# Figure1.net
KiCad netlist of a schematic drawn in Altium Designer
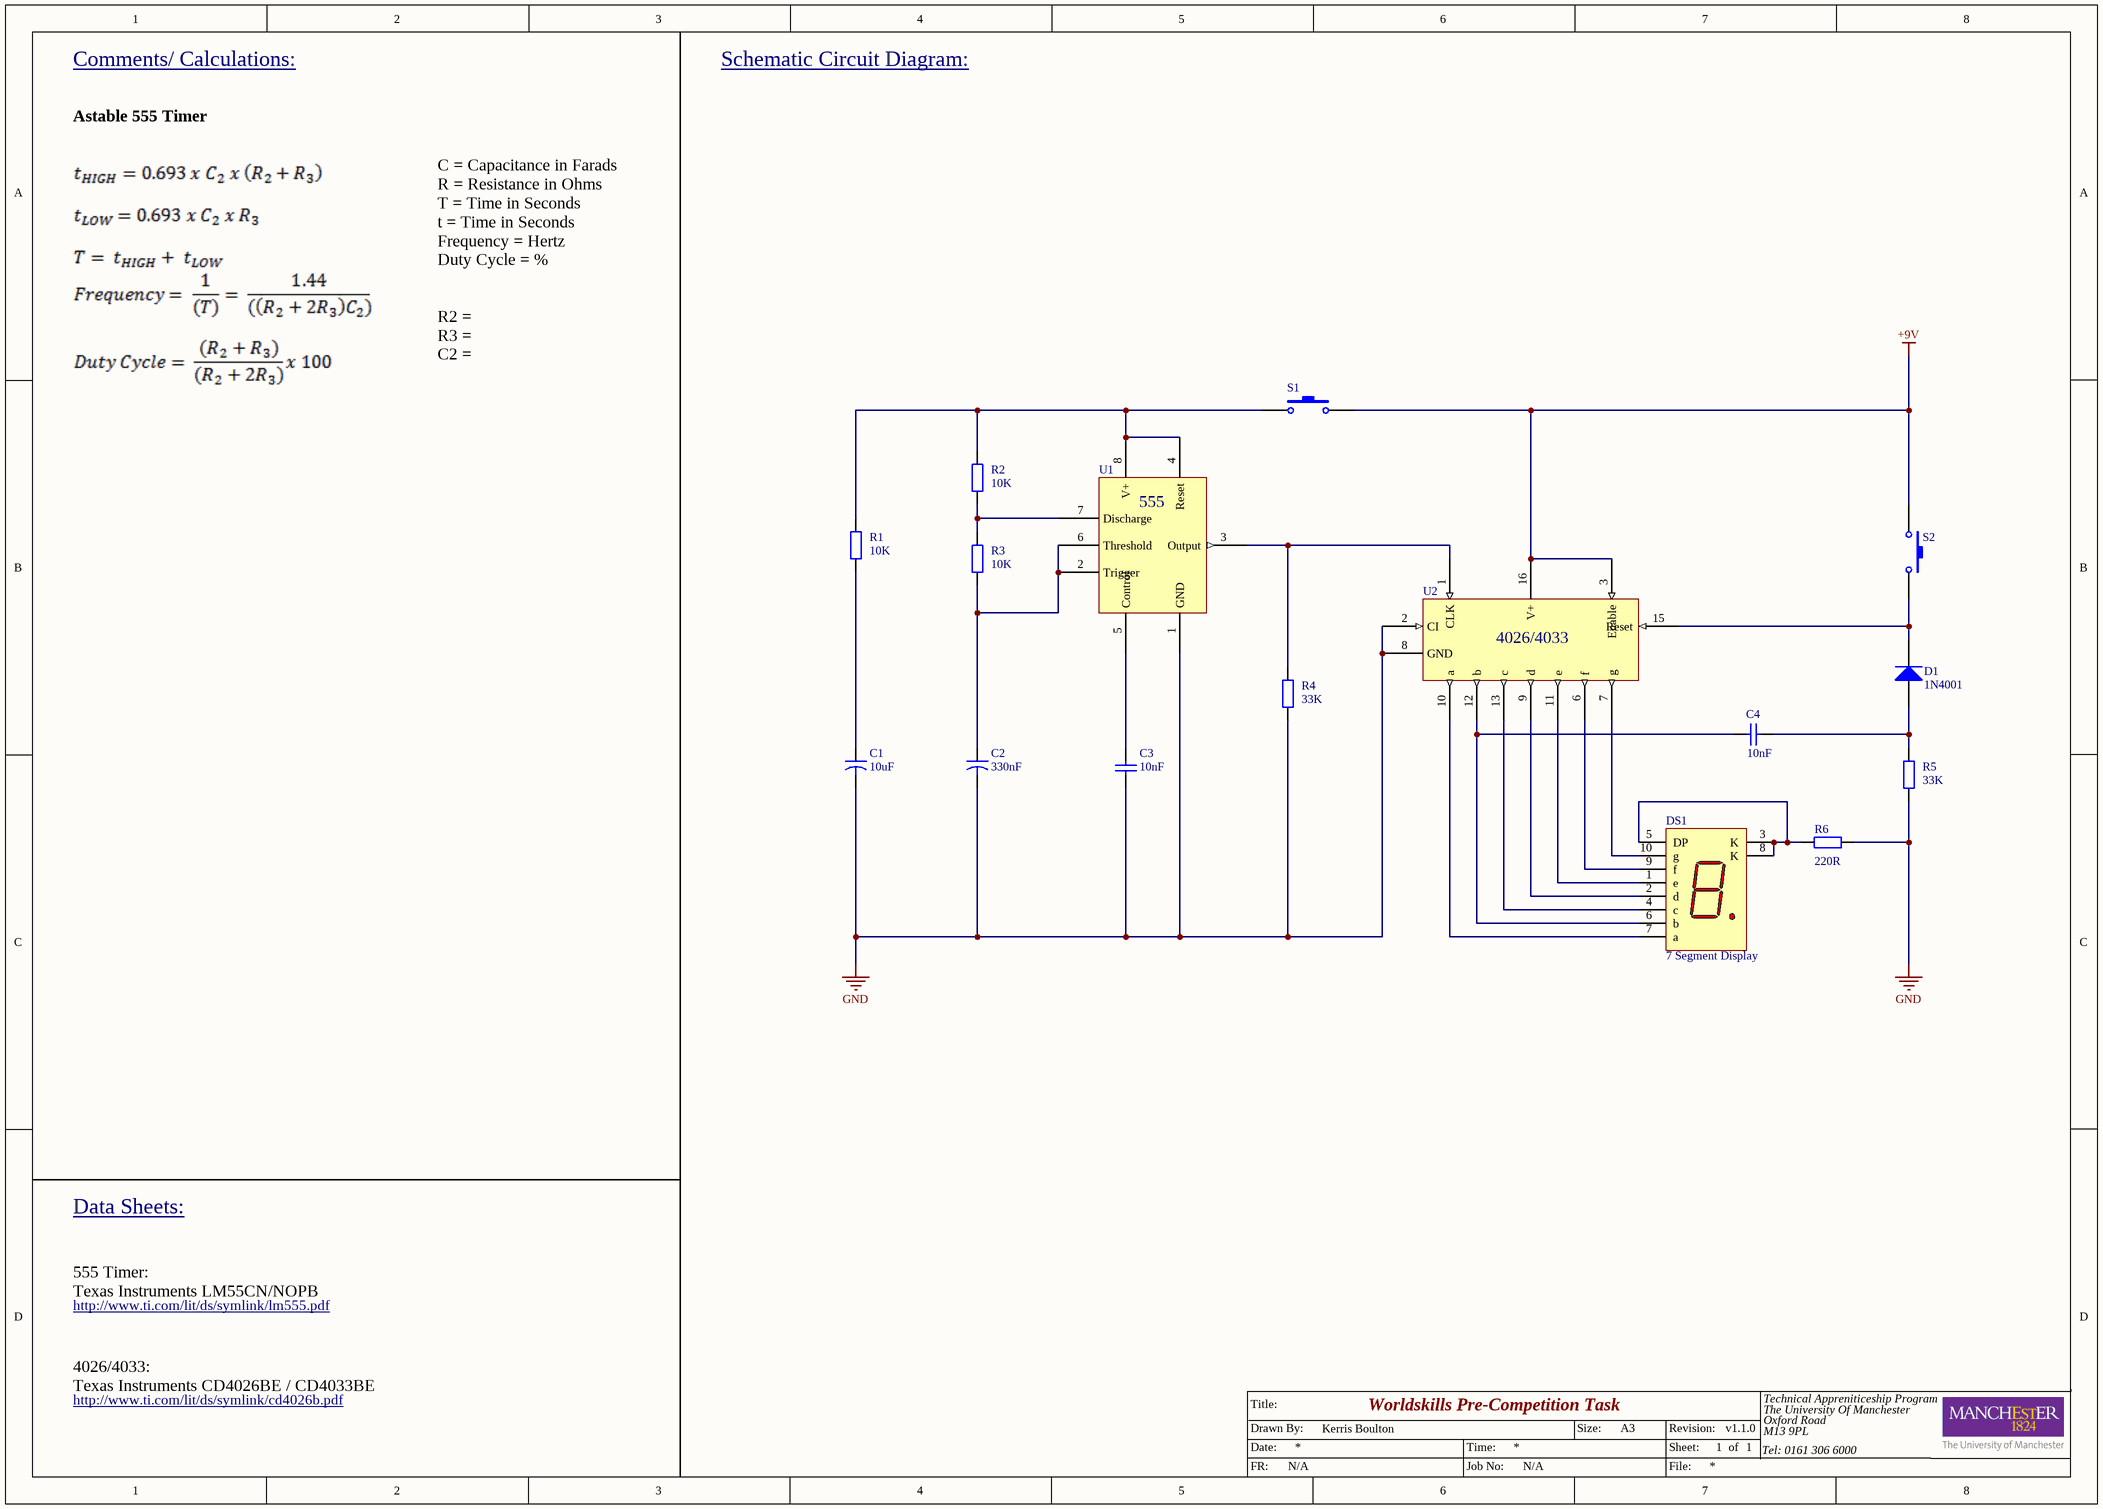
[diagram p0: Figure1.SchDoc]

(export (version "E")
  (design (tool "Eeschema 10.0.6"))
  (components
    (comp (ref "C1")
      (value "10uF")
      (footprint "CAPR5-4X5")
      (description "Capacitor")
      (fields (field (name "PUBLISHER") "Altium Limited"))
      (libsource (lib "Miscellaneous Devices") (part "Cap2"))
    )
    (comp (ref "C2")
      (value "330nF")
      (footprint "CAPR5-4X5")
      (description "Capacitor")
      (fields (field (name "PUBLISHER") "Altium Limited"))
      (libsource (lib "Miscellaneous Devices") (part "Cap2"))
    )
    (comp (ref "C3")
      (value "10nF")
      (footprint "RAD-0.3")
      (description "Capacitor")
      (fields (field (name "PUBLISHER") "Altium Limited"))
      (libsource (lib "Miscellaneous Devices") (part "Cap"))
    )
    (comp (ref "C4")
      (value "10nF")
      (footprint "RAD-0.3")
      (description "Capacitor")
      (fields (field (name "PUBLISHER") "Altium Limited"))
      (libsource (lib "Miscellaneous Devices") (part "Cap"))
    )
    (comp (ref "D1")
      (value "1N4001")
      (footprint "DO-41")
      (description "1 Amp General Purpose Rectifier")
      (fields (field (name "PUBLISHER") "Altium Limited"))
      (libsource (lib "Miscellaneous Devices") (part "Diode 1N4001"))
    )
    (comp (ref "DS1")
      (value "7 Segment Display")
      (footprint "A")
      (fields (field (name "PUBLISHER") "Altium Limited"))
      (libsource (lib "Miscellaneous Devices") (part "Dpy Red-CC"))
    )
    (comp (ref "R1")
      (value "10K")
      (footprint "AXIAL-0.4")
      (description "Resistor")
      (fields (field (name "PUBLISHER") "Altium Limited"))
      (libsource (lib "") (part "Res2_1"))
    )
    (comp (ref "R2")
      (value "10K")
      (footprint "AXIAL-0.4")
      (description "Resistor")
      (fields (field (name "PUBLISHER") "Altium Limited"))
      (libsource (lib "") (part "Res2_1"))
    )
    (comp (ref "R3")
      (value "10K")
      (footprint "AXIAL-0.4")
      (description "Resistor")
      (fields (field (name "PUBLISHER") "Altium Limited"))
      (libsource (lib "") (part "Res2_1"))
    )
    (comp (ref "R4")
      (value "33K")
      (footprint "AXIAL-0.4")
      (description "Resistor")
      (fields (field (name "PUBLISHER") "Altium Limited"))
      (libsource (lib "") (part "Res2_1"))
    )
    (comp (ref "R5")
      (value "33K")
      (footprint "AXIAL-0.4")
      (description "Resistor")
      (fields (field (name "PUBLISHER") "Altium Limited"))
      (libsource (lib "") (part "Res2_1"))
    )
    (comp (ref "R6")
      (value "220R")
      (footprint "AXIAL-0.4")
      (description "Resistor")
      (fields (field (name "PUBLISHER") "Altium Limited"))
      (libsource (lib "Miscellaneous Devices") (part "Res2"))
    )
    (comp (ref "S1")
      (value "SW-PB")
      (footprint "SPST-2")
      (description "SPST Switch")
      (fields (field (name "PUBLISHER") "Altium Limited"))
      (libsource (lib "Miscellaneous Devices") (part "SW-PB"))
    )
    (comp (ref "S2")
      (value "SW-PB")
      (footprint "SPST-2")
      (description "SPST Switch")
      (fields (field (name "PUBLISHER") "Altium Limited"))
      (libsource (lib "Miscellaneous Devices") (part "SW-PB"))
    )
    (comp (ref "U1")
      (value "555")
      (footprint "555")
      (description "555 Timer")
      (libsource (lib "Worldskills Pre-Comp Lib") (part "555 TIMER"))
    )
    (comp (ref "U2")
      (value "4026/4033")
      (footprint "4026/4033")
      (description "Decade Counter/Divider")
      (libsource (lib "Worldskills Pre-Comp Lib") (part "4026/4033"))
    )
  )
  (nets
    (net (code "1") (name "+9V") (class "Default")
      (node (ref "S1") (pin "2") (pinfunction "2_2") (pintype "passive"))
      (node (ref "S2") (pin "1") (pinfunction "1_1") (pintype "passive"))
      (node (ref "U2") (pin "16") (pinfunction "V+_16") (pintype "power_in"))
      (node (ref "U2") (pin "3") (pinfunction "Enable_3") (pintype "input"))
    )
    (net (code "2") (name "GND") (class "Default")
      (node (ref "C1") (pin "2") (pinfunction "2_2") (pintype "passive"))
      (node (ref "C2") (pin "2") (pinfunction "2_2") (pintype "passive"))
      (node (ref "C3") (pin "1") (pinfunction "1_1") (pintype "passive"))
      (node (ref "R4") (pin "1") (pinfunction "1_1") (pintype "passive"))
      (node (ref "R5") (pin "1") (pinfunction "1_1") (pintype "passive"))
      (node (ref "R6") (pin "2") (pinfunction "2_2") (pintype "passive"))
      (node (ref "U1") (pin "1") (pinfunction "GND_1") (pintype "power_in"))
      (node (ref "U2") (pin "2") (pinfunction "CI_2") (pintype "input"))
      (node (ref "U2") (pin "8") (pinfunction "GND_8") (pintype "power_in"))
    )
    (net (code "3") (name "Net-(C1-Pad1)") (class "Default")
      (node (ref "C1") (pin "1") (pinfunction "1_1") (pintype "passive"))
      (node (ref "R1") (pin "1") (pinfunction "1_1") (pintype "passive"))
    )
    (net (code "4") (name "Net-(D1-A)") (class "Default")
      (node (ref "C4") (pin "2") (pinfunction "2_2") (pintype "passive"))
      (node (ref "D1") (pin "1") (pinfunction "A_1") (pintype "passive"))
      (node (ref "R5") (pin "2") (pinfunction "2_2") (pintype "passive"))
    )
    (net (code "5") (name "Net-(D1-K)") (class "Default")
      (node (ref "D1") (pin "2") (pinfunction "K_2") (pintype "passive"))
      (node (ref "S2") (pin "2") (pinfunction "2_2") (pintype "passive"))
      (node (ref "U2") (pin "15") (pinfunction "Reset_15") (pintype "input"))
    )
    (net (code "6") (name "Net-(DS1-DP)") (class "Default")
      (node (ref "DS1") (pin "3") (pinfunction "K_3") (pintype "passive"))
      (node (ref "DS1") (pin "5") (pinfunction "DP_5") (pintype "passive"))
      (node (ref "DS1") (pin "8") (pinfunction "K_8") (pintype "passive"))
      (node (ref "R6") (pin "1") (pinfunction "1_1") (pintype "passive"))
    )
    (net (code "7") (name "Net-(DS1-a)") (class "Default")
      (node (ref "DS1") (pin "7") (pinfunction "a_7") (pintype "passive"))
      (node (ref "U2") (pin "10") (pinfunction "a_10") (pintype "output"))
    )
    (net (code "8") (name "Net-(DS1-b)") (class "Default")
      (node (ref "C4") (pin "1") (pinfunction "1_1") (pintype "passive"))
      (node (ref "DS1") (pin "6") (pinfunction "b_6") (pintype "passive"))
      (node (ref "U2") (pin "12") (pinfunction "b_12") (pintype "output"))
    )
    (net (code "9") (name "Net-(DS1-c)") (class "Default")
      (node (ref "DS1") (pin "4") (pinfunction "c_4") (pintype "passive"))
      (node (ref "U2") (pin "13") (pinfunction "c_13") (pintype "output"))
    )
    (net (code "10") (name "Net-(DS1-d)") (class "Default")
      (node (ref "DS1") (pin "2") (pinfunction "d_2") (pintype "passive"))
      (node (ref "U2") (pin "9") (pinfunction "d_9") (pintype "output"))
    )
    (net (code "11") (name "Net-(DS1-e)") (class "Default")
      (node (ref "DS1") (pin "1") (pinfunction "e_1") (pintype "passive"))
      (node (ref "U2") (pin "11") (pinfunction "e_11") (pintype "output"))
    )
    (net (code "12") (name "Net-(DS1-f)") (class "Default")
      (node (ref "DS1") (pin "9") (pinfunction "f_9") (pintype "passive"))
      (node (ref "U2") (pin "6") (pinfunction "f_6") (pintype "output"))
    )
    (net (code "13") (name "Net-(DS1-g)") (class "Default")
      (node (ref "DS1") (pin "10") (pinfunction "g_10") (pintype "passive"))
      (node (ref "U2") (pin "7") (pinfunction "g_7") (pintype "output"))
    )
    (net (code "14") (name "Net-(U1-Control)") (class "Default")
      (node (ref "C3") (pin "2") (pinfunction "2_2") (pintype "passive"))
      (node (ref "U1") (pin "5") (pinfunction "Control_5") (pintype "passive"))
    )
    (net (code "15") (name "Net-(U1-Discharge)") (class "Default")
      (node (ref "R2") (pin "1") (pinfunction "1_1") (pintype "passive"))
      (node (ref "R3") (pin "2") (pinfunction "2_2") (pintype "passive"))
      (node (ref "U1") (pin "7") (pinfunction "Discharge_7") (pintype "passive"))
    )
    (net (code "16") (name "Net-(U1-Output)") (class "Default")
      (node (ref "R4") (pin "2") (pinfunction "2_2") (pintype "passive"))
      (node (ref "U1") (pin "3") (pinfunction "Output_3") (pintype "output"))
      (node (ref "U2") (pin "1") (pinfunction "CLK_1") (pintype "input"))
    )
    (net (code "17") (name "Net-(U1-Reset)") (class "Default")
      (node (ref "R1") (pin "2") (pinfunction "2_2") (pintype "passive"))
      (node (ref "R2") (pin "2") (pinfunction "2_2") (pintype "passive"))
      (node (ref "S1") (pin "1") (pinfunction "1_1") (pintype "passive"))
      (node (ref "U1") (pin "4") (pinfunction "Reset_4") (pintype "passive"))
      (node (ref "U1") (pin "8") (pinfunction "V+_8") (pintype "power_in"))
    )
    (net (code "18") (name "Net-(U1-Threshold)") (class "Default")
      (node (ref "C2") (pin "1") (pinfunction "1_1") (pintype "passive"))
      (node (ref "R3") (pin "1") (pinfunction "1_1") (pintype "passive"))
      (node (ref "U1") (pin "2") (pinfunction "Trigger_2") (pintype "passive"))
      (node (ref "U1") (pin "6") (pinfunction "Threshold_6") (pintype "passive"))
    )
  )
)
